# ZenithWatch.net
KiCad netlist of a schematic drawn in EAGLE
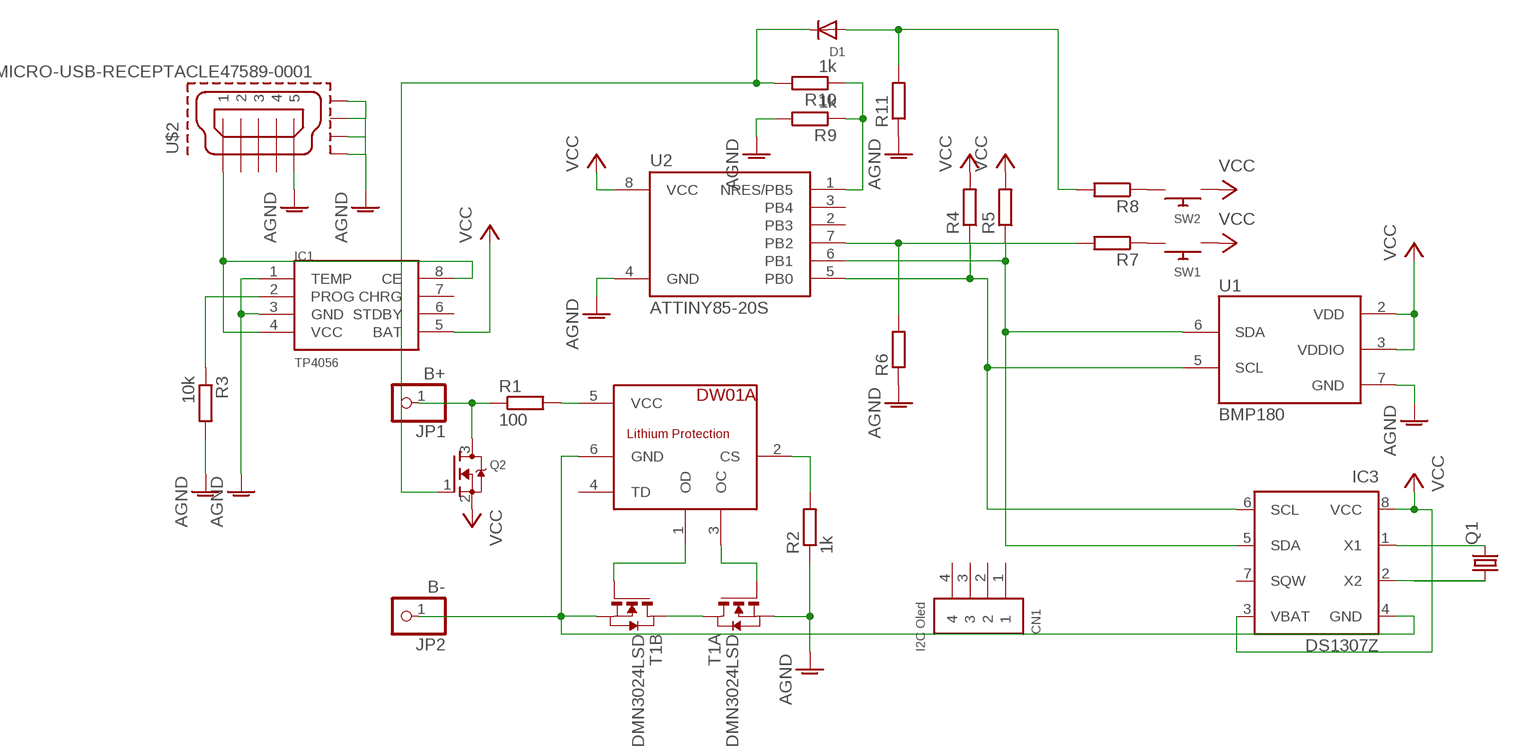
[diagram p0: schematic, sheet 1]

(export (version "E")
  (design (tool "Eeschema 10.0.6"))
  (components
    (comp (ref "CN1")
      (value "I2C Oled")
      (footprint "eagle-import:1X04-BIG")
      (libsource (lib "eagle-import") (part "1X4-BIG"))
    )
    (comp (ref "D1")
      (value "DIODESOT23_REFLOW")
      (footprint "eagle-import:SOT23-R")
      (libsource (lib "eagle-import") (part "DIODESOT23_REFLOW"))
    )
    (comp (ref "IC1")
      (value "TP4056")
      (footprint "eagle-import:SOP-8")
      (libsource (lib "eagle-import") (part "TP4056"))
    )
    (comp (ref "IC3")
      (value "DS1307Z")
      (footprint "eagle-import:SOIC8")
      (libsource (lib "eagle-import") (part "DS1307Z"))
    )
    (comp (ref "JP1")
      (value "B+")
      (footprint "eagle-import:1X01")
      (libsource (lib "eagle-import") (part "PINHD-1X1"))
    )
    (comp (ref "JP2")
      (value "B-")
      (footprint "eagle-import:1X01")
      (libsource (lib "eagle-import") (part "PINHD-1X1"))
    )
    (comp (ref "Q1")
      (value "CRYSTALCTS406")
      (footprint "eagle-import:CTS406")
      (libsource (lib "eagle-import") (part "CRYSTALCTS406"))
    )
    (comp (ref "Q2")
      (value "MOSFET-NREFLOW")
      (footprint "eagle-import:SOT23")
      (libsource (lib "eagle-import") (part "MOSFET-NREFLOW"))
    )
    (comp (ref "R1")
      (value "100")
      (footprint "eagle-import:R0603")
      (libsource (lib "eagle-import") (part "R-EU_R0603"))
    )
    (comp (ref "R2")
      (value "1k")
      (footprint "eagle-import:R0603")
      (libsource (lib "eagle-import") (part "R-EU_R0603"))
    )
    (comp (ref "R3")
      (value "10k")
      (footprint "eagle-import:R0603")
      (libsource (lib "eagle-import") (part "R-EU_R0603"))
    )
    (comp (ref "R4")
      (value "R-EU_R0603")
      (footprint "eagle-import:R0603")
      (libsource (lib "eagle-import") (part "R-EU_R0603"))
    )
    (comp (ref "R5")
      (value "R-EU_R0603")
      (footprint "eagle-import:R0603")
      (libsource (lib "eagle-import") (part "R-EU_R0603"))
    )
    (comp (ref "R6")
      (value "R-EU_R0603")
      (footprint "eagle-import:R0603")
      (libsource (lib "eagle-import") (part "R-EU_R0603"))
    )
    (comp (ref "R7")
      (value "R-EU_R0603")
      (footprint "eagle-import:R0603")
      (libsource (lib "eagle-import") (part "R-EU_R0603"))
    )
    (comp (ref "R8")
      (value "R-EU_R0603")
      (footprint "eagle-import:R0603")
      (libsource (lib "eagle-import") (part "R-EU_R0603"))
    )
    (comp (ref "R9")
      (value "1k")
      (footprint "eagle-import:R0603")
      (libsource (lib "eagle-import") (part "R-EU_R0603"))
    )
    (comp (ref "R10")
      (value "1k")
      (footprint "eagle-import:R0603")
      (libsource (lib "eagle-import") (part "R-EU_R0603"))
    )
    (comp (ref "R11")
      (value "R-EU_R0603")
      (footprint "eagle-import:R0603")
      (libsource (lib "eagle-import") (part "R-EU_R0603"))
    )
    (comp (ref "SW1")
      (value "SWITCH_PUSHBUTTONC&K_KSS")
      (footprint "eagle-import:BTN_CK_KSS")
      (libsource (lib "eagle-import") (part "SWITCH_PUSHBUTTONC&K_KSS"))
    )
    (comp (ref "SW2")
      (value "SWITCH_PUSHBUTTONC&K_KSS")
      (footprint "eagle-import:BTN_CK_KSS")
      (libsource (lib "eagle-import") (part "SWITCH_PUSHBUTTONC&K_KSS"))
    )
    (comp (ref "T1")
      (value "DMN3024LSD")
      (footprint "eagle-import:TSSOP-8")
      (libsource (lib "eagle-import") (part "DMN3024LSD"))
    )
    (comp (ref "U$1")
      (value "DW01A")
      (footprint "eagle-import:SOT23-6")
      (libsource (lib "eagle-import") (part "DW01A"))
    )
    (comp (ref "U$2")
      (value "MICRO-USB-RECEPTACLE47589-0001")
      (footprint "eagle-import:47589-0001")
      (libsource (lib "eagle-import") (part "MICRO-USB-RECEPTACLE47589-0001"))
    )
    (comp (ref "U1")
      (value "BMP180")
      (footprint "eagle-import:BMP180")
      (libsource (lib "eagle-import") (part "BMP180"))
    )
    (comp (ref "U2")
      (value "ATTINY85-20S")
      (footprint "eagle-import:SOIC8_EIAJ_208MIL")
      (libsource (lib "eagle-import") (part "ATTINY85S-20"))
    )
  )
  (nets
    (net (code "1") (name "AGND") (class "Default")
      (node (ref "IC1") (pin "1") (pinfunction "TEMP_1") (pintype "bidirectional"))
      (node (ref "IC1") (pin "3") (pinfunction "GND_3") (pintype "bidirectional"))
      (node (ref "R11") (pin "1") (pinfunction "1_1") (pintype "passive"))
      (node (ref "R2") (pin "1") (pinfunction "1_1") (pintype "passive"))
      (node (ref "R3") (pin "2") (pinfunction "2_2") (pintype "passive"))
      (node (ref "R6") (pin "1") (pinfunction "1_1") (pintype "passive"))
      (node (ref "R9") (pin "2") (pinfunction "2_2") (pintype "passive"))
      (node (ref "T1") (pin "2") (pinfunction "S_2") (pintype "passive"))
      (node (ref "T1") (pin "3") (pinfunction "S_3") (pintype "passive"))
      (node (ref "U$2") (pin "5") (pinfunction "5_5") (pintype "input"))
      (node (ref "U$2") (pin "CASING1") (pinfunction "GND1_CASING1") (pintype "bidirectional"))
      (node (ref "U$2") (pin "CASING2") (pinfunction "GND2_CASING2") (pintype "bidirectional"))
      (node (ref "U$2") (pin "CASING3") (pinfunction "GND3_CASING3") (pintype "bidirectional"))
      (node (ref "U$2") (pin "CASING4") (pinfunction "GND4_CASING4") (pintype "bidirectional"))
      (node (ref "U1") (pin "7") (pinfunction "GND_7") (pintype "power_in"))
      (node (ref "U2") (pin "4") (pinfunction "GND_4") (pintype "power_in"))
    )
    (net (code "2") (name "Net-(D1-A)") (class "Default")
      (node (ref "D1") (pin "1") (pinfunction "A_1") (pintype "passive"))
      (node (ref "R11") (pin "2") (pinfunction "2_2") (pintype "passive"))
      (node (ref "R8") (pin "2") (pinfunction "2_2") (pintype "passive"))
    )
    (net (code "3") (name "Net-(D1-C)") (class "Default")
      (node (ref "D1") (pin "3") (pinfunction "C_3") (pintype "passive"))
      (node (ref "Q2") (pin "1") (pinfunction "G_1") (pintype "bidirectional"))
      (node (ref "R10") (pin "2") (pinfunction "2_2") (pintype "passive"))
    )
    (net (code "4") (name "Net-(IC1-CE)") (class "Default")
      (node (ref "IC1") (pin "4") (pinfunction "VCC_4") (pintype "bidirectional"))
      (node (ref "IC1") (pin "8") (pinfunction "CE_8") (pintype "bidirectional"))
      (node (ref "U$2") (pin "1") (pinfunction "1_1") (pintype "input"))
    )
    (net (code "5") (name "Net-(IC1-PROG)") (class "Default")
      (node (ref "IC1") (pin "2") (pinfunction "PROG_2") (pintype "bidirectional"))
      (node (ref "R3") (pin "1") (pinfunction "1_1") (pintype "passive"))
    )
    (net (code "6") (name "Net-(IC3-GND)") (class "Default")
      (node (ref "IC3") (pin "4") (pinfunction "GND_4") (pintype "power_in"))
      (node (ref "JP2") (pin "1") (pinfunction "1_1") (pintype "passive"))
      (node (ref "T1") (pin "6") (pinfunction "S_6") (pintype "passive"))
      (node (ref "T1") (pin "7") (pinfunction "S_7") (pintype "passive"))
      (node (ref "U$1") (pin "6") (pinfunction "GND_6") (pintype "bidirectional"))
    )
    (net (code "7") (name "Net-(IC3-SCL)") (class "Default")
      (node (ref "IC3") (pin "6") (pinfunction "SCL_6") (pintype "input"))
      (node (ref "R4") (pin "1") (pinfunction "1_1") (pintype "passive"))
      (node (ref "U1") (pin "5") (pinfunction "SCL_5") (pintype "input"))
      (node (ref "U2") (pin "5") (pinfunction "PB0_5") (pintype "bidirectional"))
    )
    (net (code "8") (name "Net-(IC3-SDA)") (class "Default")
      (node (ref "IC3") (pin "5") (pinfunction "SDA_5") (pintype "bidirectional"))
      (node (ref "R5") (pin "1") (pinfunction "1_1") (pintype "passive"))
      (node (ref "U1") (pin "6") (pinfunction "SDA_6") (pintype "bidirectional"))
      (node (ref "U2") (pin "6") (pinfunction "PB1_6") (pintype "bidirectional"))
    )
    (net (code "9") (name "Net-(IC3-X1)") (class "Default")
      (node (ref "IC3") (pin "1") (pinfunction "X1_1") (pintype "input"))
      (node (ref "Q1") (pin "3") (pinfunction "2_3") (pintype "passive"))
    )
    (net (code "10") (name "Net-(IC3-X2)") (class "Default")
      (node (ref "IC3") (pin "2") (pinfunction "X2_2") (pintype "output"))
      (node (ref "Q1") (pin "1") (pinfunction "1_1") (pintype "passive"))
    )
    (net (code "11") (name "Net-(Q2-D)") (class "Default")
      (node (ref "JP1") (pin "1") (pinfunction "1_1") (pintype "passive"))
      (node (ref "Q2") (pin "3") (pinfunction "D_3") (pintype "bidirectional"))
      (node (ref "R1") (pin "1") (pinfunction "1_1") (pintype "passive"))
    )
    (net (code "12") (name "Net-(R7-Pad1)") (class "Default")
      (node (ref "R7") (pin "1") (pinfunction "1_1") (pintype "passive"))
      (node (ref "SW1") (pin "P$2") (pinfunction "P$2_P$2") (pintype "passive"))
    )
    (net (code "13") (name "Net-(R8-Pad1)") (class "Default")
      (node (ref "R8") (pin "1") (pinfunction "1_1") (pintype "passive"))
      (node (ref "SW2") (pin "P$2") (pinfunction "P$2_P$2") (pintype "passive"))
    )
    (net (code "14") (name "Net-(T1A-D)") (class "Default")
      (node (ref "T1") (pin "1") (pinfunction "D_1") (pintype "passive"))
      (node (ref "T1") (pin "8") (pinfunction "D_8") (pintype "passive"))
    )
    (net (code "15") (name "Net-(T1A-G)") (class "Default")
      (node (ref "T1") (pin "4") (pinfunction "G_4") (pintype "passive"))
      (node (ref "U$1") (pin "3") (pinfunction "OC_3") (pintype "bidirectional"))
    )
    (net (code "16") (name "Net-(T1B-G)") (class "Default")
      (node (ref "T1") (pin "5") (pinfunction "G_5") (pintype "passive"))
      (node (ref "U$1") (pin "1") (pinfunction "OD_1") (pintype "bidirectional"))
    )
    (net (code "17") (name "Net-(U$1-CS)") (class "Default")
      (node (ref "R2") (pin "2") (pinfunction "2_2") (pintype "passive"))
      (node (ref "U$1") (pin "2") (pinfunction "CS_2") (pintype "bidirectional"))
    )
    (net (code "18") (name "Net-(U$1-VCC)") (class "Default")
      (node (ref "R1") (pin "2") (pinfunction "2_2") (pintype "passive"))
      (node (ref "U$1") (pin "5") (pinfunction "VCC_5") (pintype "bidirectional"))
    )
    (net (code "19") (name "Net-(U2-NRES{slash}PB5)") (class "Default")
      (node (ref "R10") (pin "1") (pinfunction "1_1") (pintype "passive"))
      (node (ref "R9") (pin "1") (pinfunction "1_1") (pintype "passive"))
      (node (ref "U2") (pin "1") (pinfunction "NRES/PB5_1") (pintype "bidirectional"))
    )
    (net (code "20") (name "Net-(U2-PB2)") (class "Default")
      (node (ref "R6") (pin "2") (pinfunction "2_2") (pintype "passive"))
      (node (ref "R7") (pin "2") (pinfunction "2_2") (pintype "passive"))
      (node (ref "U2") (pin "7") (pinfunction "PB2_7") (pintype "bidirectional"))
    )
    (net (code "21") (name "VCC") (class "Default")
      (node (ref "IC1") (pin "5") (pinfunction "BAT_5") (pintype "bidirectional"))
      (node (ref "IC3") (pin "3") (pinfunction "VBAT_3") (pintype "passive"))
      (node (ref "IC3") (pin "8") (pinfunction "VCC_8") (pintype "power_in"))
      (node (ref "Q2") (pin "2") (pinfunction "S_2") (pintype "bidirectional"))
      (node (ref "R4") (pin "2") (pinfunction "2_2") (pintype "passive"))
      (node (ref "R5") (pin "2") (pinfunction "2_2") (pintype "passive"))
      (node (ref "SW1") (pin "P$1") (pinfunction "P$1_P$1") (pintype "passive"))
      (node (ref "SW2") (pin "P$1") (pinfunction "P$1_P$1") (pintype "passive"))
      (node (ref "U1") (pin "2") (pinfunction "VDD_2") (pintype "power_in"))
      (node (ref "U1") (pin "3") (pinfunction "VDDIO_3") (pintype "power_in"))
      (node (ref "U2") (pin "8") (pinfunction "VCC_8") (pintype "power_in"))
    )
    (net (code "22") (name "unconnected-(CN1-Pad1)") (class "Default")
      (node (ref "CN1") (pin "1") (pinfunction "1_1") (pintype "bidirectional"))
    )
    (net (code "23") (name "unconnected-(CN1-Pad2)") (class "Default")
      (node (ref "CN1") (pin "2") (pinfunction "2_2") (pintype "bidirectional"))
    )
    (net (code "24") (name "unconnected-(CN1-Pad3)") (class "Default")
      (node (ref "CN1") (pin "3") (pinfunction "3_3") (pintype "bidirectional"))
    )
    (net (code "25") (name "unconnected-(CN1-Pad4)") (class "Default")
      (node (ref "CN1") (pin "4") (pinfunction "4_4") (pintype "bidirectional"))
    )
    (net (code "26") (name "unconnected-(IC1-CHRG-Pad7)") (class "Default")
      (node (ref "IC1") (pin "7") (pinfunction "CHRG_7") (pintype "bidirectional"))
    )
    (net (code "27") (name "unconnected-(IC1-STDBY-Pad6)") (class "Default")
      (node (ref "IC1") (pin "6") (pinfunction "STDBY_6") (pintype "bidirectional"))
    )
    (net (code "28") (name "unconnected-(IC3-SQW-Pad7)") (class "Default")
      (node (ref "IC3") (pin "7") (pinfunction "SQW_7") (pintype "open_collector"))
    )
    (net (code "29") (name "unconnected-(U$1-TD-Pad4)") (class "Default")
      (node (ref "U$1") (pin "4") (pinfunction "TD_4") (pintype "bidirectional"))
    )
    (net (code "30") (name "unconnected-(U$2-Pad2)") (class "Default")
      (node (ref "U$2") (pin "2") (pinfunction "2_2") (pintype "input"))
    )
    (net (code "31") (name "unconnected-(U$2-Pad3)") (class "Default")
      (node (ref "U$2") (pin "3") (pinfunction "3_3") (pintype "input"))
    )
    (net (code "32") (name "unconnected-(U$2-Pad4)") (class "Default")
      (node (ref "U$2") (pin "4") (pinfunction "4_4") (pintype "input"))
    )
    (net (code "33") (name "unconnected-(U2-PB3-Pad2)") (class "Default")
      (node (ref "U2") (pin "2") (pinfunction "PB3_2") (pintype "bidirectional"))
    )
    (net (code "34") (name "unconnected-(U2-PB4-Pad3)") (class "Default")
      (node (ref "U2") (pin "3") (pinfunction "PB4_3") (pintype "bidirectional"))
    )
  )
)
